# Clock_1to20_Buffer.net
KiCad netlist of a schematic drawn in Altium Designer
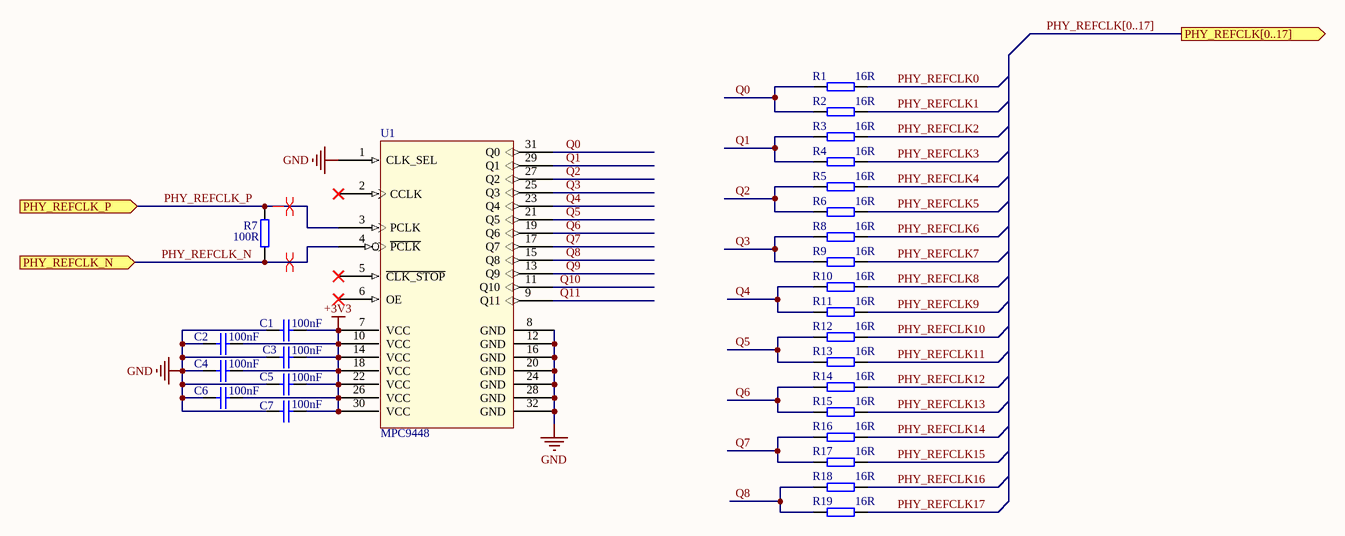
[diagram p0: Clock_1to20_Buffer.SchDoc]

(export (version "E")
  (design (tool "Eeschema 10.0.6"))
  (components
    (comp (ref "C1")
      (value "100nF")
      (footprint "CC1608-0603")
      (description "Capacitor")
      (fields
        (field (name "TOLERANCE") "±10%")
        (field (name "VOLTAGE") "16V")
        (field (name "PUBLISHER") "Altium Limited")
      )
      (libsource (lib "wr_switch") (part "Cap"))
    )
    (comp (ref "C2")
      (value "100nF")
      (footprint "CC1608-0603")
      (description "Capacitor")
      (fields
        (field (name "TOLERANCE") "±10%")
        (field (name "VOLTAGE") "16V")
        (field (name "PUBLISHER") "Altium Limited")
      )
      (libsource (lib "wr_switch") (part "Cap"))
    )
    (comp (ref "C3")
      (value "100nF")
      (footprint "CC1608-0603")
      (description "Capacitor")
      (fields
        (field (name "TOLERANCE") "±10%")
        (field (name "VOLTAGE") "16V")
        (field (name "PUBLISHER") "Altium Limited")
      )
      (libsource (lib "wr_switch") (part "Cap"))
    )
    (comp (ref "C4")
      (value "100nF")
      (footprint "CC1608-0603")
      (description "Capacitor")
      (fields
        (field (name "TOLERANCE") "±10%")
        (field (name "VOLTAGE") "16V")
        (field (name "PUBLISHER") "Altium Limited")
      )
      (libsource (lib "wr_switch") (part "Cap"))
    )
    (comp (ref "C5")
      (value "100nF")
      (footprint "CC1608-0603")
      (description "Capacitor")
      (fields
        (field (name "TOLERANCE") "±10%")
        (field (name "VOLTAGE") "16V")
        (field (name "PUBLISHER") "Altium Limited")
      )
      (libsource (lib "wr_switch") (part "Cap"))
    )
    (comp (ref "C6")
      (value "100nF")
      (footprint "CC1608-0603")
      (description "Capacitor")
      (fields
        (field (name "TOLERANCE") "±10%")
        (field (name "VOLTAGE") "16V")
        (field (name "PUBLISHER") "Altium Limited")
      )
      (libsource (lib "wr_switch") (part "Cap"))
    )
    (comp (ref "C7")
      (value "100nF")
      (footprint "CC1608-0603")
      (description "Capacitor")
      (fields
        (field (name "TOLERANCE") "±10%")
        (field (name "VOLTAGE") "16V")
        (field (name "PUBLISHER") "Altium Limited")
      )
      (libsource (lib "wr_switch") (part "Cap"))
    )
    (comp (ref "R1")
      (value "16R")
      (footprint "0603")
      (description "SMD Resistor")
      (fields (field (name "TOLERANCE") "±1%"))
      (libsource (lib "wr_switch") (part "RES_SMD"))
    )
    (comp (ref "R2")
      (value "16R")
      (footprint "0603")
      (description "SMD Resistor")
      (fields (field (name "TOLERANCE") "±1%"))
      (libsource (lib "wr_switch") (part "RES_SMD"))
    )
    (comp (ref "R3")
      (value "16R")
      (footprint "0603")
      (description "SMD Resistor")
      (fields (field (name "TOLERANCE") "±1%"))
      (libsource (lib "wr_switch") (part "RES_SMD"))
    )
    (comp (ref "R4")
      (value "16R")
      (footprint "0603")
      (description "SMD Resistor")
      (fields (field (name "TOLERANCE") "±1%"))
      (libsource (lib "wr_switch") (part "RES_SMD"))
    )
    (comp (ref "R5")
      (value "16R")
      (footprint "0603")
      (description "SMD Resistor")
      (fields (field (name "TOLERANCE") "±1%"))
      (libsource (lib "wr_switch") (part "RES_SMD"))
    )
    (comp (ref "R6")
      (value "16R")
      (footprint "0603")
      (description "SMD Resistor")
      (fields (field (name "TOLERANCE") "±1%"))
      (libsource (lib "wr_switch") (part "RES_SMD"))
    )
    (comp (ref "R7")
      (value "100R")
      (footprint "0603")
      (description "SMD Resistor")
      (fields (field (name "TOLERANCE") "±1%"))
      (libsource (lib "wr_switch") (part "RES_SMD"))
    )
    (comp (ref "R8")
      (value "16R")
      (footprint "0603")
      (description "SMD Resistor")
      (fields (field (name "TOLERANCE") "±1%"))
      (libsource (lib "wr_switch") (part "RES_SMD"))
    )
    (comp (ref "R9")
      (value "16R")
      (footprint "0603")
      (description "SMD Resistor")
      (fields (field (name "TOLERANCE") "±1%"))
      (libsource (lib "wr_switch") (part "RES_SMD"))
    )
    (comp (ref "R10")
      (value "16R")
      (footprint "0603")
      (description "SMD Resistor")
      (fields (field (name "TOLERANCE") "±1%"))
      (libsource (lib "wr_switch") (part "RES_SMD"))
    )
    (comp (ref "R11")
      (value "16R")
      (footprint "0603")
      (description "SMD Resistor")
      (fields (field (name "TOLERANCE") "±1%"))
      (libsource (lib "wr_switch") (part "RES_SMD"))
    )
    (comp (ref "R12")
      (value "16R")
      (footprint "0603")
      (description "SMD Resistor")
      (fields (field (name "TOLERANCE") "±1%"))
      (libsource (lib "wr_switch") (part "RES_SMD"))
    )
    (comp (ref "R13")
      (value "16R")
      (footprint "0603")
      (description "SMD Resistor")
      (fields (field (name "TOLERANCE") "±1%"))
      (libsource (lib "wr_switch") (part "RES_SMD"))
    )
    (comp (ref "R14")
      (value "16R")
      (footprint "0603")
      (description "SMD Resistor")
      (fields (field (name "TOLERANCE") "±1%"))
      (libsource (lib "wr_switch") (part "RES_SMD"))
    )
    (comp (ref "R15")
      (value "16R")
      (footprint "0603")
      (description "SMD Resistor")
      (fields (field (name "TOLERANCE") "±1%"))
      (libsource (lib "wr_switch") (part "RES_SMD"))
    )
    (comp (ref "R16")
      (value "16R")
      (footprint "0603")
      (description "SMD Resistor")
      (fields (field (name "TOLERANCE") "±1%"))
      (libsource (lib "wr_switch") (part "RES_SMD"))
    )
    (comp (ref "R17")
      (value "16R")
      (footprint "0603")
      (description "SMD Resistor")
      (fields (field (name "TOLERANCE") "±1%"))
      (libsource (lib "wr_switch") (part "RES_SMD"))
    )
    (comp (ref "R18")
      (value "16R")
      (footprint "0603")
      (description "SMD Resistor")
      (fields (field (name "TOLERANCE") "±1%"))
      (libsource (lib "wr_switch") (part "RES_SMD"))
    )
    (comp (ref "R19")
      (value "16R")
      (footprint "0603")
      (description "SMD Resistor")
      (fields (field (name "TOLERANCE") "±1%"))
      (libsource (lib "wr_switch") (part "RES_SMD"))
    )
    (comp (ref "U1")
      (value "MPC9448")
      (footprint "QFP80P900X900X160-32AN")
      (description "3.3V/2.5V LVCMOS 1:12 Low Skew Clock Fanout Buffer")
      (libsource (lib "wr_switch") (part "MPC9448"))
    )
  )
  (nets
    (net (code "1") (name "+3V3") (class "Default")
      (node (ref "C1") (pin "1") (pinfunction "1_1") (pintype "passive"))
      (node (ref "C2") (pin "1") (pinfunction "1_1") (pintype "passive"))
      (node (ref "C3") (pin "1") (pinfunction "1_1") (pintype "passive"))
      (node (ref "C4") (pin "1") (pinfunction "1_1") (pintype "passive"))
      (node (ref "C5") (pin "1") (pinfunction "1_1") (pintype "passive"))
      (node (ref "C6") (pin "1") (pinfunction "1_1") (pintype "passive"))
      (node (ref "C7") (pin "1") (pinfunction "1_1") (pintype "passive"))
      (node (ref "U1") (pin "10") (pinfunction "VCC_10") (pintype "power_in"))
      (node (ref "U1") (pin "14") (pinfunction "VCC_14") (pintype "power_in"))
      (node (ref "U1") (pin "18") (pinfunction "VCC_18") (pintype "power_in"))
      (node (ref "U1") (pin "22") (pinfunction "VCC_22") (pintype "power_in"))
      (node (ref "U1") (pin "26") (pinfunction "VCC_26") (pintype "power_in"))
      (node (ref "U1") (pin "30") (pinfunction "VCC_30") (pintype "power_in"))
      (node (ref "U1") (pin "7") (pinfunction "VCC_7") (pintype "power_in"))
    )
    (net (code "2") (name "/PHY_REFCLK0") (class "Default")
      (node (ref "R1") (pin "2") (pinfunction "2_2") (pintype "passive"))
    )
    (net (code "3") (name "/PHY_REFCLK1") (class "Default")
      (node (ref "R2") (pin "2") (pinfunction "2_2") (pintype "passive"))
    )
    (net (code "4") (name "/PHY_REFCLK2") (class "Default")
      (node (ref "R3") (pin "2") (pinfunction "2_2") (pintype "passive"))
    )
    (net (code "5") (name "/PHY_REFCLK3") (class "Default")
      (node (ref "R4") (pin "2") (pinfunction "2_2") (pintype "passive"))
    )
    (net (code "6") (name "/PHY_REFCLK4") (class "Default")
      (node (ref "R5") (pin "2") (pinfunction "2_2") (pintype "passive"))
    )
    (net (code "7") (name "/PHY_REFCLK5") (class "Default")
      (node (ref "R6") (pin "2") (pinfunction "2_2") (pintype "passive"))
    )
    (net (code "8") (name "/PHY_REFCLK6") (class "Default")
      (node (ref "R8") (pin "2") (pinfunction "2_2") (pintype "passive"))
    )
    (net (code "9") (name "/PHY_REFCLK7") (class "Default")
      (node (ref "R9") (pin "2") (pinfunction "2_2") (pintype "passive"))
    )
    (net (code "10") (name "/PHY_REFCLK8") (class "Default")
      (node (ref "R10") (pin "2") (pinfunction "2_2") (pintype "passive"))
    )
    (net (code "11") (name "/PHY_REFCLK9") (class "Default")
      (node (ref "R11") (pin "2") (pinfunction "2_2") (pintype "passive"))
    )
    (net (code "12") (name "/PHY_REFCLK10") (class "Default")
      (node (ref "R12") (pin "2") (pinfunction "2_2") (pintype "passive"))
    )
    (net (code "13") (name "/PHY_REFCLK11") (class "Default")
      (node (ref "R13") (pin "2") (pinfunction "2_2") (pintype "passive"))
    )
    (net (code "14") (name "/PHY_REFCLK12") (class "Default")
      (node (ref "R14") (pin "2") (pinfunction "2_2") (pintype "passive"))
    )
    (net (code "15") (name "/PHY_REFCLK13") (class "Default")
      (node (ref "R15") (pin "2") (pinfunction "2_2") (pintype "passive"))
    )
    (net (code "16") (name "/PHY_REFCLK14") (class "Default")
      (node (ref "R16") (pin "2") (pinfunction "2_2") (pintype "passive"))
    )
    (net (code "17") (name "/PHY_REFCLK15") (class "Default")
      (node (ref "R17") (pin "2") (pinfunction "2_2") (pintype "passive"))
    )
    (net (code "18") (name "/PHY_REFCLK16") (class "Default")
      (node (ref "R18") (pin "2") (pinfunction "2_2") (pintype "passive"))
    )
    (net (code "19") (name "/PHY_REFCLK17") (class "Default")
      (node (ref "R19") (pin "2") (pinfunction "2_2") (pintype "passive"))
    )
    (net (code "21") (name "/PHY_REFCLK_N") (class "Default")
      (node (ref "R7") (pin "2") (pinfunction "2_2") (pintype "passive"))
      (node (ref "U1") (pin "4") (pinfunction "~{PCLK}_4") (pintype "input"))
    )
    (net (code "22") (name "/PHY_REFCLK_P") (class "Default")
      (node (ref "R7") (pin "1") (pinfunction "1_1") (pintype "passive"))
      (node (ref "U1") (pin "3") (pinfunction "PCLK_3") (pintype "input"))
    )
    (net (code "23") (name "/Q0") (class "Default")
      (node (ref "R1") (pin "1") (pinfunction "1_1") (pintype "passive"))
      (node (ref "R2") (pin "1") (pinfunction "1_1") (pintype "passive"))
      (node (ref "U1") (pin "31") (pinfunction "Q0_31") (pintype "output"))
    )
    (net (code "24") (name "/Q1") (class "Default")
      (node (ref "R3") (pin "1") (pinfunction "1_1") (pintype "passive"))
      (node (ref "R4") (pin "1") (pinfunction "1_1") (pintype "passive"))
      (node (ref "U1") (pin "29") (pinfunction "Q1_29") (pintype "output"))
    )
    (net (code "25") (name "/Q2") (class "Default")
      (node (ref "R5") (pin "1") (pinfunction "1_1") (pintype "passive"))
      (node (ref "R6") (pin "1") (pinfunction "1_1") (pintype "passive"))
      (node (ref "U1") (pin "27") (pinfunction "Q2_27") (pintype "output"))
    )
    (net (code "26") (name "/Q3") (class "Default")
      (node (ref "R8") (pin "1") (pinfunction "1_1") (pintype "passive"))
      (node (ref "R9") (pin "1") (pinfunction "1_1") (pintype "passive"))
      (node (ref "U1") (pin "25") (pinfunction "Q3_25") (pintype "output"))
    )
    (net (code "27") (name "/Q4") (class "Default")
      (node (ref "R10") (pin "1") (pinfunction "1_1") (pintype "passive"))
      (node (ref "R11") (pin "1") (pinfunction "1_1") (pintype "passive"))
      (node (ref "U1") (pin "23") (pinfunction "Q4_23") (pintype "output"))
    )
    (net (code "28") (name "/Q5") (class "Default")
      (node (ref "R12") (pin "1") (pinfunction "1_1") (pintype "passive"))
      (node (ref "R13") (pin "1") (pinfunction "1_1") (pintype "passive"))
      (node (ref "U1") (pin "21") (pinfunction "Q5_21") (pintype "output"))
    )
    (net (code "29") (name "/Q6") (class "Default")
      (node (ref "R14") (pin "1") (pinfunction "1_1") (pintype "passive"))
      (node (ref "R15") (pin "1") (pinfunction "1_1") (pintype "passive"))
      (node (ref "U1") (pin "19") (pinfunction "Q6_19") (pintype "output"))
    )
    (net (code "30") (name "/Q7") (class "Default")
      (node (ref "R16") (pin "1") (pinfunction "1_1") (pintype "passive"))
      (node (ref "R17") (pin "1") (pinfunction "1_1") (pintype "passive"))
      (node (ref "U1") (pin "17") (pinfunction "Q7_17") (pintype "output"))
    )
    (net (code "31") (name "/Q8") (class "Default")
      (node (ref "R18") (pin "1") (pinfunction "1_1") (pintype "passive"))
      (node (ref "R19") (pin "1") (pinfunction "1_1") (pintype "passive"))
      (node (ref "U1") (pin "15") (pinfunction "Q8_15") (pintype "output"))
    )
    (net (code "32") (name "/Q9") (class "Default")
      (node (ref "U1") (pin "13") (pinfunction "Q9_13") (pintype "output"))
    )
    (net (code "33") (name "/Q10") (class "Default")
      (node (ref "U1") (pin "11") (pinfunction "Q10_11") (pintype "output"))
    )
    (net (code "34") (name "/Q11") (class "Default")
      (node (ref "U1") (pin "9") (pinfunction "Q11_9") (pintype "output"))
    )
    (net (code "35") (name "GND") (class "Default")
      (node (ref "C1") (pin "2") (pinfunction "2_2") (pintype "passive"))
      (node (ref "C2") (pin "2") (pinfunction "2_2") (pintype "passive"))
      (node (ref "C3") (pin "2") (pinfunction "2_2") (pintype "passive"))
      (node (ref "C4") (pin "2") (pinfunction "2_2") (pintype "passive"))
      (node (ref "C5") (pin "2") (pinfunction "2_2") (pintype "passive"))
      (node (ref "C6") (pin "2") (pinfunction "2_2") (pintype "passive"))
      (node (ref "C7") (pin "2") (pinfunction "2_2") (pintype "passive"))
      (node (ref "U1") (pin "1") (pinfunction "CLK_SEL_1") (pintype "input"))
      (node (ref "U1") (pin "12") (pinfunction "GND_12") (pintype "power_in"))
      (node (ref "U1") (pin "16") (pinfunction "GND_16") (pintype "power_in"))
      (node (ref "U1") (pin "20") (pinfunction "GND_20") (pintype "power_in"))
      (node (ref "U1") (pin "24") (pinfunction "GND_24") (pintype "power_in"))
      (node (ref "U1") (pin "28") (pinfunction "GND_28") (pintype "power_in"))
      (node (ref "U1") (pin "32") (pinfunction "GND_32") (pintype "power_in"))
      (node (ref "U1") (pin "8") (pinfunction "GND_8") (pintype "power_in"))
    )
    (net (code "36") (name "unconnected-(U1-CCLK-Pad2)") (class "Default")
      (node (ref "U1") (pin "2") (pinfunction "CCLK_2") (pintype "input+no_connect"))
    )
    (net (code "37") (name "unconnected-(U1-OE-Pad6)") (class "Default")
      (node (ref "U1") (pin "6") (pinfunction "OE_6") (pintype "input+no_connect"))
    )
    (net (code "38") (name "unconnected-(U1-~{CLK_STOP}-Pad5)") (class "Default")
      (node (ref "U1") (pin "5") (pinfunction "~{CLK_STOP}_5") (pintype "input+no_connect"))
    )
  )
)
